# motherboard_Sheet.net
KiCad netlist of a schematic drawn in Altium Designer
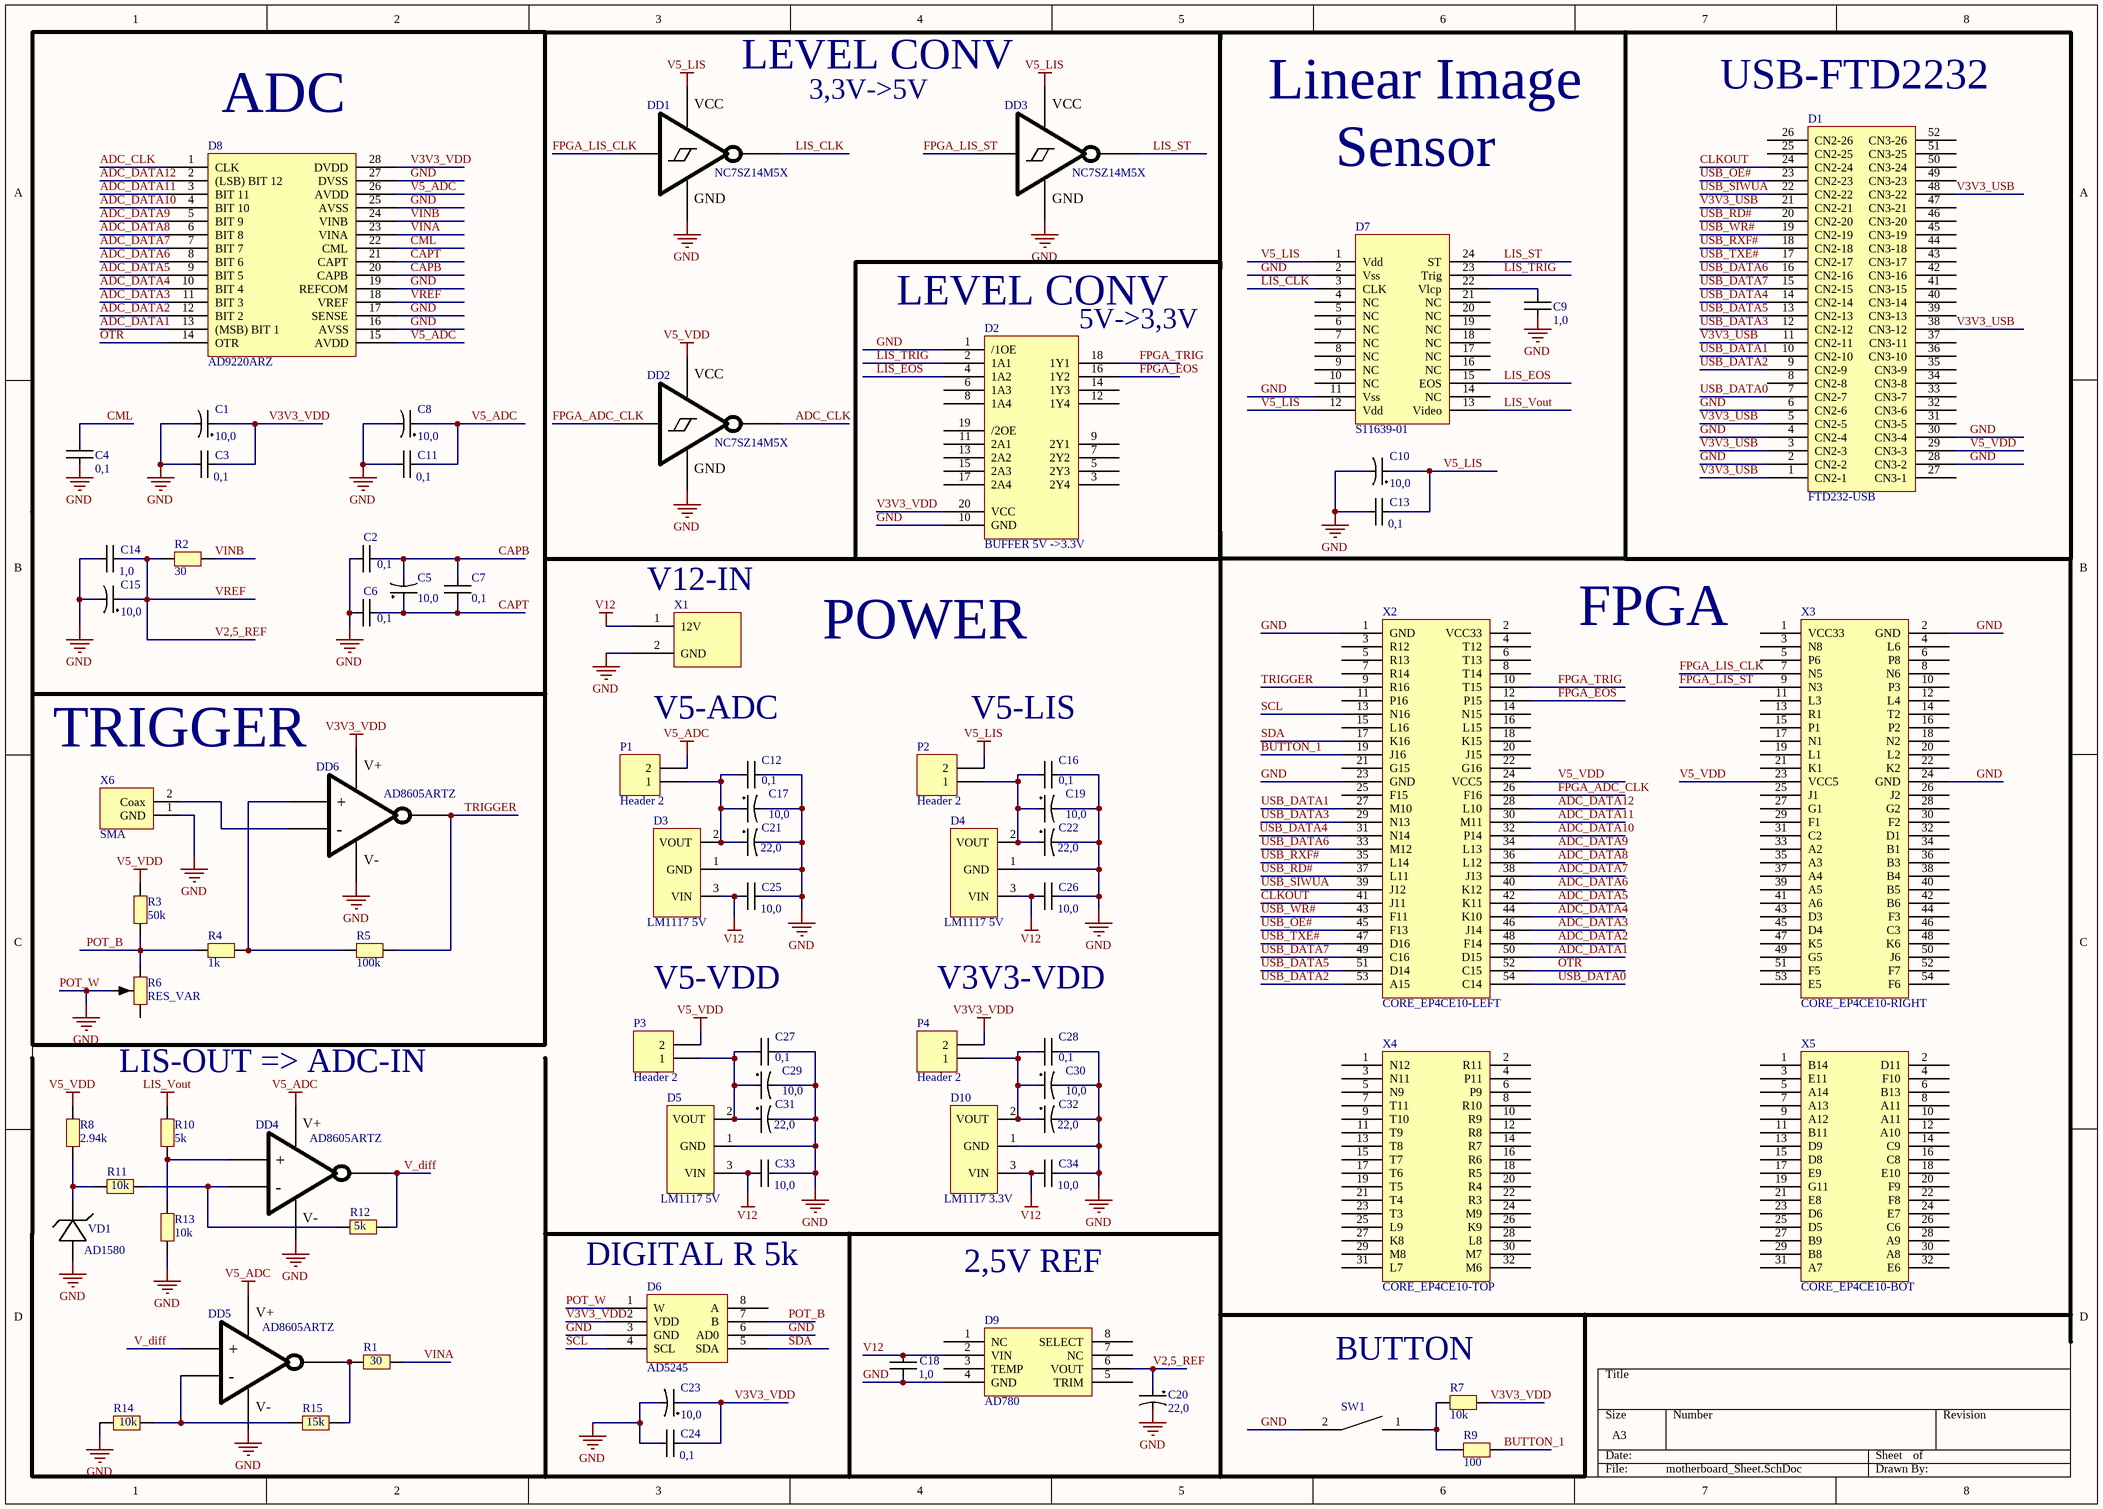
[diagram p0: motherboard_Sheet.SchDoc]

(export (version "E")
  (design (tool "Eeschema 10.0.6"))
  (components
    (comp (ref "C1")
      (value "10,0")
      (footprint "TYPE_C")
      (description "SMD")
      (libsource (lib "MIT_Schlib") (part "CAP_TANT"))
    )
    (comp (ref "C2")
      (value "0,1")
      (footprint "0805")
      (description "0805")
      (libsource (lib "MIT_Schlib") (part "CAP_SMALL"))
    )
    (comp (ref "C3")
      (value "0,1")
      (footprint "0805")
      (description "0805")
      (libsource (lib "MIT_Schlib") (part "CAP_SMALL"))
    )
    (comp (ref "C4")
      (value "0,1")
      (footprint "0805")
      (description "0805")
      (libsource (lib "MIT_Schlib") (part "CAP_SMALL"))
    )
    (comp (ref "C5")
      (value "10,0")
      (footprint "TYPE_C")
      (description "SMD")
      (libsource (lib "MIT_Schlib") (part "CAP_TANT"))
    )
    (comp (ref "C6")
      (value "0,1")
      (footprint "0805")
      (description "0805")
      (libsource (lib "MIT_Schlib") (part "CAP_SMALL"))
    )
    (comp (ref "C7")
      (value "0,1")
      (footprint "0805")
      (description "0805")
      (libsource (lib "MIT_Schlib") (part "CAP_SMALL"))
    )
    (comp (ref "C8")
      (value "10,0")
      (footprint "TYPE_C")
      (description "SMD")
      (libsource (lib "MIT_Schlib") (part "CAP_TANT"))
    )
    (comp (ref "C9")
      (value "1,0")
      (footprint "0805")
      (description "0805")
      (libsource (lib "MIT_Schlib") (part "CAP_SMALL"))
    )
    (comp (ref "C10")
      (value "10,0")
      (footprint "TYPE_C")
      (description "SMD")
      (libsource (lib "MIT_Schlib") (part "CAP_TANT"))
    )
    (comp (ref "C11")
      (value "0,1")
      (footprint "0805")
      (description "0805")
      (libsource (lib "MIT_Schlib") (part "CAP_SMALL"))
    )
    (comp (ref "C12")
      (value "0,1")
      (footprint "0805")
      (description "0805")
      (libsource (lib "MIT_Schlib") (part "CAP_SMALL"))
    )
    (comp (ref "C13")
      (value "0,1")
      (footprint "0805")
      (description "0805")
      (libsource (lib "MIT_Schlib") (part "CAP_SMALL"))
    )
    (comp (ref "C14")
      (value "1,0")
      (footprint "0805")
      (description "0805")
      (libsource (lib "MIT_Schlib") (part "CAP_SMALL"))
    )
    (comp (ref "C15")
      (value "10,0")
      (footprint "TYPE_C")
      (description "SMD")
      (libsource (lib "MIT_Schlib") (part "CAP_TANT"))
    )
    (comp (ref "C16")
      (value "0,1")
      (footprint "0805")
      (description "0805")
      (libsource (lib "MIT_Schlib") (part "CAP_SMALL"))
    )
    (comp (ref "C17")
      (value "10,0")
      (footprint "TYPE_C")
      (description "SMD")
      (libsource (lib "MIT_Schlib") (part "CAP_TANT"))
    )
    (comp (ref "C18")
      (value "1,0")
      (footprint "0805")
      (description "0805")
      (libsource (lib "MIT_Schlib") (part "CAP_SMALL"))
    )
    (comp (ref "C19")
      (value "10,0")
      (footprint "TYPE_C")
      (description "SMD")
      (libsource (lib "MIT_Schlib") (part "CAP_TANT"))
    )
    (comp (ref "C20")
      (value "22,0")
      (footprint "TYPE_C")
      (description "SMD")
      (libsource (lib "MIT_Schlib") (part "CAP_TANT"))
    )
    (comp (ref "C21")
      (value "22,0")
      (footprint "TYPE_C")
      (description "SMD")
      (libsource (lib "MIT_Schlib") (part "CAP_TANT"))
    )
    (comp (ref "C22")
      (value "22,0")
      (footprint "TYPE_C")
      (description "SMD")
      (libsource (lib "MIT_Schlib") (part "CAP_TANT"))
    )
    (comp (ref "C23")
      (value "10,0")
      (footprint "TYPE_C")
      (description "SMD")
      (libsource (lib "MIT_Schlib") (part "CAP_TANT"))
    )
    (comp (ref "C24")
      (value "0,1")
      (footprint "0805")
      (description "0805")
      (libsource (lib "MIT_Schlib") (part "CAP_SMALL"))
    )
    (comp (ref "C25")
      (value "10,0")
      (footprint "0805")
      (description "0805")
      (libsource (lib "MIT_Schlib") (part "CAP_SMALL"))
    )
    (comp (ref "C26")
      (value "10,0")
      (footprint "0805")
      (description "0805")
      (libsource (lib "MIT_Schlib") (part "CAP_SMALL"))
    )
    (comp (ref "C27")
      (value "0,1")
      (footprint "0805")
      (description "0805")
      (libsource (lib "MIT_Schlib") (part "CAP_SMALL"))
    )
    (comp (ref "C28")
      (value "0,1")
      (footprint "0805")
      (description "0805")
      (libsource (lib "MIT_Schlib") (part "CAP_SMALL"))
    )
    (comp (ref "C29")
      (value "10,0")
      (footprint "TYPE_C")
      (description "SMD")
      (libsource (lib "MIT_Schlib") (part "CAP_TANT"))
    )
    (comp (ref "C30")
      (value "10,0")
      (footprint "TYPE_C")
      (description "SMD")
      (libsource (lib "MIT_Schlib") (part "CAP_TANT"))
    )
    (comp (ref "C31")
      (value "22,0")
      (footprint "TYPE_C")
      (description "SMD")
      (libsource (lib "MIT_Schlib") (part "CAP_TANT"))
    )
    (comp (ref "C32")
      (value "22,0")
      (footprint "TYPE_C")
      (description "SMD")
      (libsource (lib "MIT_Schlib") (part "CAP_TANT"))
    )
    (comp (ref "C33")
      (value "10,0")
      (footprint "0805")
      (description "0805")
      (libsource (lib "MIT_Schlib") (part "CAP_SMALL"))
    )
    (comp (ref "C34")
      (value "10,0")
      (footprint "0805")
      (description "0805")
      (libsource (lib "MIT_Schlib") (part "CAP_SMALL"))
    )
    (comp (ref "D1")
      (value "FTD232-USB")
      (footprint "ftd232_minimodule")
      (libsource (lib "MIT_Schlib") (part "ftd232_minimodule"))
    )
    (comp (ref "D2")
      (value "BUFFER 5V ->3.3V")
      (footprint "SN74LVC244ADWR")
      (libsource (lib "MIT_Schlib") (part "SN74LVC244ADWR"))
    )
    (comp (ref "D3")
      (value "LM1117 5V")
      (footprint "TO-252")
      (description "LM1117-FIX")
      (libsource (lib "MIT_Schlib") (part "LM1117_FIX"))
    )
    (comp (ref "D4")
      (value "LM1117 5V")
      (footprint "TO-252")
      (description "LM1117-FIX")
      (libsource (lib "MIT_Schlib") (part "LM1117_FIX"))
    )
    (comp (ref "D5")
      (value "LM1117 5V")
      (footprint "TO-252")
      (description "LM1117-FIX")
      (libsource (lib "MIT_Schlib") (part "LM1117_FIX"))
    )
    (comp (ref "D6") (value "AD5245") (footprint "AD5245") (libsource (lib "MIT_Schlib") (part "AD5245")))
    (comp (ref "D7")
      (value "S11639-01")
      (footprint "s11639-01")
      (libsource (lib "MIT_Schlib") (part "S11639-01"))
    )
    (comp (ref "D8")
      (value "AD9220ARZ")
      (footprint "SOP28")
      (libsource (lib "MIT_Schlib") (part "AD9220ARZ"))
    )
    (comp (ref "D9") (value "AD780") (footprint "SOP8") (libsource (lib "MIT_Schlib") (part "AD780")))
    (comp (ref "D10")
      (value "LM1117 3.3V")
      (footprint "TO-252")
      (description "LM1117-FIX")
      (libsource (lib "MIT_Schlib") (part "LM1117_FIX"))
    )
    (comp (ref "DD1")
      (value "NC7SZ14M5X")
      (footprint "SOT-23-5")
      (libsource (lib "MIT_Schlib") (part "NC7SZ14M5X"))
    )
    (comp (ref "DD2")
      (value "NC7SZ14M5X")
      (footprint "SOT-23-5")
      (libsource (lib "MIT_Schlib") (part "NC7SZ14M5X"))
    )
    (comp (ref "DD3")
      (value "NC7SZ14M5X")
      (footprint "SOT-23-5")
      (libsource (lib "MIT_Schlib") (part "NC7SZ14M5X"))
    )
    (comp (ref "DD4")
      (value "AD8605ARTZ")
      (footprint "SOT-23-5")
      (libsource (lib "MIT_Schlib") (part "AD8605ARTZ"))
    )
    (comp (ref "DD5")
      (value "AD8605ARTZ")
      (footprint "SOT-23-5")
      (libsource (lib "MIT_Schlib") (part "AD8605ARTZ"))
    )
    (comp (ref "DD6")
      (value "AD8605ARTZ")
      (footprint "SOT-23-5")
      (libsource (lib "MIT_Schlib") (part "AD8605ARTZ"))
    )
    (comp (ref "P1")
      (value "Header 2")
      (footprint "HDR1X2")
      (description "Header, 2-Pin")
      (fields (field (name "PUBLISHER") "Altium Limited"))
      (libsource (lib "Miscellaneous Connectors") (part "Header 2"))
    )
    (comp (ref "P2")
      (value "Header 2")
      (footprint "HDR1X2")
      (description "Header, 2-Pin")
      (fields (field (name "PUBLISHER") "Altium Limited"))
      (libsource (lib "Miscellaneous Connectors") (part "Header 2"))
    )
    (comp (ref "P3")
      (value "Header 2")
      (footprint "HDR1X2")
      (description "Header, 2-Pin")
      (fields (field (name "PUBLISHER") "Altium Limited"))
      (libsource (lib "Miscellaneous Connectors") (part "Header 2"))
    )
    (comp (ref "P4")
      (value "Header 2")
      (footprint "HDR1X2")
      (description "Header, 2-Pin")
      (fields (field (name "PUBLISHER") "Altium Limited"))
      (libsource (lib "Miscellaneous Connectors") (part "Header 2"))
    )
    (comp (ref "R1")
      (value "30")
      (footprint "0805")
      (description "0805")
      (libsource (lib "MIT_Schlib") (part "RES0805"))
    )
    (comp (ref "R2")
      (value "30")
      (footprint "0805")
      (description "0805")
      (libsource (lib "MIT_Schlib") (part "RES0805"))
    )
    (comp (ref "R3")
      (value "50k")
      (footprint "0805")
      (description "0805")
      (libsource (lib "") (part "RES0805_1"))
    )
    (comp (ref "R4")
      (value "1k")
      (footprint "0805")
      (description "0805")
      (libsource (lib "") (part "RES0805_3"))
    )
    (comp (ref "R5")
      (value "100k")
      (footprint "0805")
      (description "0805")
      (libsource (lib "MIT_Schlib") (part "RES0805"))
    )
    (comp (ref "R6")
      (value "RES_VAR")
      (footprint "3006P")
      (description "PV36W102C (СП5-2ВБ) 1 кОм")
      (libsource (lib "MIT_Schlib") (part "RES_VAR"))
    )
    (comp (ref "R7")
      (value "10k")
      (footprint "0805")
      (description "0805")
      (libsource (lib "MIT_Schlib") (part "RES0805"))
    )
    (comp (ref "R8")
      (value "2.94k")
      (footprint "0805")
      (description "0805")
      (libsource (lib "") (part "RES0805_1"))
    )
    (comp (ref "R9")
      (value "100")
      (footprint "0805")
      (description "0805")
      (libsource (lib "MIT_Schlib") (part "RES0805"))
    )
    (comp (ref "R10")
      (value "5k")
      (footprint "0805")
      (description "0805")
      (libsource (lib "") (part "RES0805_1"))
    )
    (comp (ref "R11")
      (value "10k")
      (footprint "0805")
      (description "0805")
      (libsource (lib "MIT_Schlib") (part "RES0805"))
    )
    (comp (ref "R12")
      (value "5k")
      (footprint "0805")
      (description "0805")
      (libsource (lib "MIT_Schlib") (part "RES0805"))
    )
    (comp (ref "R13")
      (value "10k")
      (footprint "0805")
      (description "0805")
      (libsource (lib "") (part "RES0805_2"))
    )
    (comp (ref "R14")
      (value "10k")
      (footprint "0805")
      (description "0805")
      (libsource (lib "MIT_Schlib") (part "RES0805"))
    )
    (comp (ref "R15")
      (value "15k")
      (footprint "0805")
      (description "0805")
      (libsource (lib "MIT_Schlib") (part "RES0805"))
    )
    (comp (ref "SW1") (value "BUTTON") (footprint "BUTTON") (libsource (lib "MIT_Schlib") (part "BUTTON")))
    (comp (ref "VD1") (value "AD1580") (footprint "SOT-23") (libsource (lib "MIT_Schlib") (part "AD1580")))
    (comp (ref "X1")
      (value "12V POWER")
      (footprint "Robiton-DS-210")
      (libsource (lib "MIT_Schlib") (part "ROBITON_12V"))
    )
    (comp (ref "X2")
      (value "CORE_EP4CE10-LEFT")
      (footprint "CORE_EP4CE10-LEFT")
      (libsource (lib "MIT_Schlib") (part "CORE_EP4CE10-LEFT"))
    )
    (comp (ref "X3")
      (value "CORE_EP4CE10-RIGHT")
      (footprint "CORE_EP4CE10-RIGHT")
      (libsource (lib "MIT_Schlib") (part "CORE_EP4CE10-RIGHT"))
    )
    (comp (ref "X4")
      (value "CORE_EP4CE10-TOP")
      (footprint "CORE_EP4CE10-TOP")
      (libsource (lib "MIT_Schlib") (part "CORE_EP4CE10-TOP"))
    )
    (comp (ref "X5")
      (value "CORE_EP4CE10-BOT")
      (footprint "CORE_EP4CE10-BOT")
      (libsource (lib "MIT_Schlib") (part "CORE_EP4CE10-BOT"))
    )
    (comp (ref "X6") (value "SMA") (footprint "SMA") (libsource (lib "MIT_Schlib") (part "SMA")))
  )
  (nets
    (net (code "1") (name "/ADC_CLK") (class "Default")
      (node (ref "D8") (pin "1") (pinfunction "CLK_1") (pintype "passive"))
      (node (ref "DD2") (pin "4") (pinfunction "Y_OUT_4") (pintype "passive"))
    )
    (net (code "2") (name "/ADC_DATA1") (class "Default")
      (node (ref "D8") (pin "13") (pinfunction "(MSB)_BIT_1_13") (pintype "passive"))
      (node (ref "X2") (pin "50") (pinfunction "D15_50") (pintype "passive"))
    )
    (net (code "3") (name "/ADC_DATA2") (class "Default")
      (node (ref "D8") (pin "12") (pinfunction "BIT_2_12") (pintype "passive"))
      (node (ref "X2") (pin "48") (pinfunction "F14_48") (pintype "passive"))
    )
    (net (code "4") (name "/ADC_DATA3") (class "Default")
      (node (ref "D8") (pin "11") (pinfunction "BIT_3_11") (pintype "passive"))
      (node (ref "X2") (pin "46") (pinfunction "J14_46") (pintype "passive"))
    )
    (net (code "5") (name "/ADC_DATA4") (class "Default")
      (node (ref "D8") (pin "10") (pinfunction "BIT_4_10") (pintype "passive"))
      (node (ref "X2") (pin "44") (pinfunction "K10_44") (pintype "passive"))
    )
    (net (code "6") (name "/ADC_DATA5") (class "Default")
      (node (ref "D8") (pin "9") (pinfunction "BIT_5_9") (pintype "passive"))
      (node (ref "X2") (pin "42") (pinfunction "K11_42") (pintype "passive"))
    )
    (net (code "7") (name "/ADC_DATA6") (class "Default")
      (node (ref "D8") (pin "8") (pinfunction "BIT_6_8") (pintype "passive"))
      (node (ref "X2") (pin "40") (pinfunction "K12_40") (pintype "passive"))
    )
    (net (code "8") (name "/ADC_DATA7") (class "Default")
      (node (ref "D8") (pin "7") (pinfunction "BIT_7_7") (pintype "passive"))
      (node (ref "X2") (pin "38") (pinfunction "J13_38") (pintype "passive"))
    )
    (net (code "9") (name "/ADC_DATA8") (class "Default")
      (node (ref "D8") (pin "6") (pinfunction "BIT_8_6") (pintype "passive"))
      (node (ref "X2") (pin "36") (pinfunction "L12_36") (pintype "passive"))
    )
    (net (code "10") (name "/ADC_DATA9") (class "Default")
      (node (ref "D8") (pin "5") (pinfunction "BIT_9_5") (pintype "passive"))
      (node (ref "X2") (pin "34") (pinfunction "L13_34") (pintype "passive"))
    )
    (net (code "11") (name "/ADC_DATA10") (class "Default")
      (node (ref "D8") (pin "4") (pinfunction "BIT_10_4") (pintype "passive"))
      (node (ref "X2") (pin "32") (pinfunction "P14_32") (pintype "passive"))
    )
    (net (code "12") (name "/ADC_DATA11") (class "Default")
      (node (ref "D8") (pin "3") (pinfunction "BIT_11_3") (pintype "passive"))
      (node (ref "X2") (pin "30") (pinfunction "M11_30") (pintype "passive"))
    )
    (net (code "13") (name "/ADC_DATA12") (class "Default")
      (node (ref "D8") (pin "2") (pinfunction "(LSB)_BIT_12_2") (pintype "passive"))
      (node (ref "X2") (pin "28") (pinfunction "L10_28") (pintype "passive"))
    )
    (net (code "14") (name "/BUTTON_1") (class "Default")
      (node (ref "R9") (pin "2") (pinfunction "2_2") (pintype "passive"))
      (node (ref "X2") (pin "19") (pinfunction "J16_19") (pintype "passive"))
    )
    (net (code "15") (name "/CAPB") (class "Default")
      (node (ref "C2") (pin "1") (pinfunction "1_1") (pintype "passive"))
      (node (ref "C5") (pin "1") (pinfunction "1_1") (pintype "passive"))
      (node (ref "C7") (pin "2") (pinfunction "2_2") (pintype "passive"))
      (node (ref "D8") (pin "20") (pinfunction "CAPB_20") (pintype "passive"))
    )
    (net (code "16") (name "/CAPT") (class "Default")
      (node (ref "C5") (pin "2") (pinfunction "2_2") (pintype "passive"))
      (node (ref "C6") (pin "1") (pinfunction "1_1") (pintype "passive"))
      (node (ref "C7") (pin "1") (pinfunction "1_1") (pintype "passive"))
      (node (ref "D8") (pin "21") (pinfunction "CAPT_21") (pintype "passive"))
    )
    (net (code "17") (name "/CLKOUT") (class "Default")
      (node (ref "D1") (pin "24") (pinfunction "CN2-24_24") (pintype "passive"))
      (node (ref "X2") (pin "41") (pinfunction "J11_41") (pintype "passive"))
    )
    (net (code "18") (name "/CML") (class "Default")
      (node (ref "C4") (pin "2") (pinfunction "2_2") (pintype "passive"))
      (node (ref "D8") (pin "22") (pinfunction "CML_22") (pintype "passive"))
    )
    (net (code "19") (name "/FPGA_ADC_CLK") (class "Default")
      (node (ref "DD2") (pin "2") (pinfunction "A_IN_2") (pintype "passive"))
      (node (ref "X2") (pin "26") (pinfunction "F16_26") (pintype "passive"))
    )
    (net (code "20") (name "/FPGA_EOS") (class "Default")
      (node (ref "D2") (pin "16") (pinfunction "1Y2_16") (pintype "passive"))
      (node (ref "X2") (pin "12") (pinfunction "P15_12") (pintype "passive"))
    )
    (net (code "21") (name "/FPGA_LIS_CLK") (class "Default")
      (node (ref "DD1") (pin "2") (pinfunction "A_IN_2") (pintype "passive"))
      (node (ref "X3") (pin "7") (pinfunction "N5_7") (pintype "passive"))
    )
    (net (code "22") (name "/FPGA_LIS_ST") (class "Default")
      (node (ref "DD3") (pin "2") (pinfunction "A_IN_2") (pintype "passive"))
      (node (ref "X3") (pin "9") (pinfunction "N3_9") (pintype "passive"))
    )
    (net (code "23") (name "/FPGA_TRIG") (class "Default")
      (node (ref "D2") (pin "18") (pinfunction "1Y1_18") (pintype "passive"))
      (node (ref "X2") (pin "10") (pinfunction "T15_10") (pintype "passive"))
    )
    (net (code "24") (name "/LIS_CLK") (class "Default")
      (node (ref "D7") (pin "3") (pinfunction "CLK_3") (pintype "passive"))
      (node (ref "DD1") (pin "4") (pinfunction "Y_OUT_4") (pintype "passive"))
    )
    (net (code "25") (name "/LIS_EOS") (class "Default")
      (node (ref "D2") (pin "4") (pinfunction "1A2_4") (pintype "passive"))
      (node (ref "D7") (pin "15") (pinfunction "EOS_15") (pintype "passive"))
    )
    (net (code "26") (name "/LIS_ST") (class "Default")
      (node (ref "D7") (pin "24") (pinfunction "ST_24") (pintype "passive"))
      (node (ref "DD3") (pin "4") (pinfunction "Y_OUT_4") (pintype "passive"))
    )
    (net (code "27") (name "/LIS_TRIG") (class "Default")
      (node (ref "D2") (pin "2") (pinfunction "1A1_2") (pintype "passive"))
      (node (ref "D7") (pin "23") (pinfunction "Trig_23") (pintype "passive"))
    )
    (net (code "28") (name "/OTR") (class "Default")
      (node (ref "D8") (pin "14") (pinfunction "OTR_14") (pintype "passive"))
      (node (ref "X2") (pin "52") (pinfunction "C15_52") (pintype "passive"))
    )
    (net (code "29") (name "/POT_B") (class "Default")
      (node (ref "D6") (pin "7") (pinfunction "B_7") (pintype "passive"))
      (node (ref "R3") (pin "1") (pinfunction "1_1") (pintype "passive"))
      (node (ref "R4") (pin "2") (pinfunction "2_2") (pintype "passive"))
      (node (ref "R6") (pin "1") (pinfunction "1_1") (pintype "passive"))
    )
    (net (code "30") (name "/SCL") (class "Default")
      (node (ref "D6") (pin "4") (pinfunction "SCL_4") (pintype "passive"))
      (node (ref "X2") (pin "13") (pinfunction "N16_13") (pintype "passive"))
    )
    (net (code "31") (name "/SDA") (class "Default")
      (node (ref "D6") (pin "5") (pinfunction "SDA_5") (pintype "passive"))
      (node (ref "X2") (pin "17") (pinfunction "K16_17") (pintype "passive"))
    )
    (net (code "32") (name "/TRIGGER") (class "Default")
      (node (ref "DD6") (pin "1") (pinfunction "OUT_1") (pintype "passive"))
      (node (ref "R5") (pin "2") (pinfunction "2_2") (pintype "passive"))
      (node (ref "X2") (pin "9") (pinfunction "R16_9") (pintype "passive"))
    )
    (net (code "33") (name "/USB_DATA0") (class "Default")
      (node (ref "D1") (pin "7") (pinfunction "CN2-7_7") (pintype "passive"))
      (node (ref "X2") (pin "54") (pinfunction "C14_54") (pintype "passive"))
    )
    (net (code "34") (name "/USB_DATA1") (class "Default")
      (node (ref "D1") (pin "10") (pinfunction "CN2-10_10") (pintype "passive"))
      (node (ref "X2") (pin "27") (pinfunction "M10_27") (pintype "passive"))
    )
    (net (code "35") (name "/USB_DATA2") (class "Default")
      (node (ref "D1") (pin "9") (pinfunction "CN2-9_9") (pintype "passive"))
      (node (ref "X2") (pin "53") (pinfunction "A15_53") (pintype "passive"))
    )
    (net (code "36") (name "/USB_DATA3") (class "Default")
      (node (ref "D1") (pin "12") (pinfunction "CN2-12_12") (pintype "passive"))
      (node (ref "X2") (pin "29") (pinfunction "N13_29") (pintype "passive"))
    )
    (net (code "37") (name "/USB_DATA4") (class "Default")
      (node (ref "D1") (pin "14") (pinfunction "CN2-14_14") (pintype "passive"))
      (node (ref "X2") (pin "31") (pinfunction "N14_31") (pintype "passive"))
    )
    (net (code "38") (name "/USB_DATA5") (class "Default")
      (node (ref "D1") (pin "13") (pinfunction "CN2-13_13") (pintype "passive"))
      (node (ref "X2") (pin "51") (pinfunction "D14_51") (pintype "passive"))
    )
    (net (code "39") (name "/USB_DATA6") (class "Default")
      (node (ref "D1") (pin "16") (pinfunction "CN2-16_16") (pintype "passive"))
      (node (ref "X2") (pin "33") (pinfunction "M12_33") (pintype "passive"))
    )
    (net (code "40") (name "/USB_DATA7") (class "Default")
      (node (ref "D1") (pin "15") (pinfunction "CN2-15_15") (pintype "passive"))
      (node (ref "X2") (pin "49") (pinfunction "C16_49") (pintype "passive"))
    )
    (net (code "41") (name "/USB_OE#") (class "Default")
      (node (ref "D1") (pin "23") (pinfunction "CN2-23_23") (pintype "passive"))
      (node (ref "X2") (pin "45") (pinfunction "F13_45") (pintype "passive"))
    )
    (net (code "42") (name "/USB_RD#") (class "Default")
      (node (ref "D1") (pin "20") (pinfunction "CN2-20_20") (pintype "passive"))
      (node (ref "X2") (pin "37") (pinfunction "L11_37") (pintype "passive"))
    )
    (net (code "43") (name "/USB_RXF#") (class "Default")
      (node (ref "D1") (pin "18") (pinfunction "CN2-18_18") (pintype "passive"))
      (node (ref "X2") (pin "35") (pinfunction "L14_35") (pintype "passive"))
    )
    (net (code "44") (name "/USB_SIWUA") (class "Default")
      (node (ref "D1") (pin "22") (pinfunction "CN2-22_22") (pintype "passive"))
      (node (ref "X2") (pin "39") (pinfunction "J12_39") (pintype "passive"))
    )
    (net (code "45") (name "/USB_TXE#") (class "Default")
      (node (ref "D1") (pin "17") (pinfunction "CN2-17_17") (pintype "passive"))
      (node (ref "X2") (pin "47") (pinfunction "D16_47") (pintype "passive"))
    )
    (net (code "46") (name "/USB_WR#") (class "Default")
      (node (ref "D1") (pin "19") (pinfunction "CN2-19_19") (pintype "passive"))
      (node (ref "X2") (pin "43") (pinfunction "F11_43") (pintype "passive"))
    )
    (net (code "47") (name "/V2,5_REF") (class "Default")
      (node (ref "C14") (pin "2") (pinfunction "2_2") (pintype "passive"))
      (node (ref "C15") (pin "2") (pinfunction "2_2") (pintype "passive"))
      (node (ref "C20") (pin "2") (pinfunction "2_2") (pintype "passive"))
      (node (ref "D8") (pin "18") (pinfunction "VREF_18") (pintype "passive"))
      (node (ref "D9") (pin "6") (pinfunction "VOUT_6") (pintype "passive"))
      (node (ref "R2") (pin "1") (pinfunction "1_1") (pintype "passive"))
    )
    (net (code "48") (name "/V3V3_USB") (class "Default")
      (node (ref "D1") (pin "1") (pinfunction "CN2-1_1") (pintype "passive"))
      (node (ref "D1") (pin "11") (pinfunction "CN2-11_11") (pintype "passive"))
      (node (ref "D1") (pin "21") (pinfunction "CN2-21_21") (pintype "passive"))
      (node (ref "D1") (pin "3") (pinfunction "CN2-3_3") (pintype "passive"))
      (node (ref "D1") (pin "38") (pinfunction "CN3-12_38") (pintype "passive"))
      (node (ref "D1") (pin "48") (pinfunction "CN3-22_48") (pintype "passive"))
      (node (ref "D1") (pin "5") (pinfunction "CN2-5_5") (pintype "passive"))
    )
    (net (code "49") (name "/VINA") (class "Default")
      (node (ref "D8") (pin "23") (pinfunction "VINA_23") (pintype "passive"))
      (node (ref "R1") (pin "2") (pinfunction "2_2") (pintype "passive"))
    )
    (net (code "50") (name "/VINB") (class "Default")
      (node (ref "D8") (pin "24") (pinfunction "VINB_24") (pintype "passive"))
      (node (ref "R2") (pin "2") (pinfunction "2_2") (pintype "passive"))
    )
    (net (code "51") (name "/V_diff") (class "Default")
      (node (ref "DD4") (pin "1") (pinfunction "OUT_1") (pintype "passive"))
      (node (ref "DD5") (pin "3") (pinfunction "+_3") (pintype "passive"))
      (node (ref "R12") (pin "2") (pinfunction "2_2") (pintype "passive"))
    )
    (net (code "52") (name "GND") (class "Default")
      (node (ref "C1") (pin "1") (pinfunction "1_1") (pintype "passive"))
      (node (ref "C10") (pin "1") (pinfunction "1_1") (pintype "passive"))
      (node (ref "C11") (pin "1") (pinfunction "1_1") (pintype "passive"))
      (node (ref "C12") (pin "1") (pinfunction "1_1") (pintype "passive"))
      (node (ref "C13") (pin "1") (pinfunction "1_1") (pintype "passive"))
      (node (ref "C14") (pin "1") (pinfunction "1_1") (pintype "passive"))
      (node (ref "C15") (pin "1") (pinfunction "1_1") (pintype "passive"))
      (node (ref "C16") (pin "1") (pinfunction "1_1") (pintype "passive"))
      (node (ref "C17") (pin "1") (pinfunction "1_1") (pintype "passive"))
      (node (ref "C18") (pin "1") (pinfunction "1_1") (pintype "passive"))
      (node (ref "C19") (pin "1") (pinfunction "1_1") (pintype "passive"))
      (node (ref "C2") (pin "2") (pinfunction "2_2") (pintype "passive"))
      (node (ref "C20") (pin "1") (pinfunction "1_1") (pintype "passive"))
      (node (ref "C21") (pin "1") (pinfunction "1_1") (pintype "passive"))
      (node (ref "C22") (pin "1") (pinfunction "1_1") (pintype "passive"))
      (node (ref "C23") (pin "1") (pinfunction "1_1") (pintype "passive"))
      (node (ref "C24") (pin "1") (pinfunction "1_1") (pintype "passive"))
      (node (ref "C25") (pin "2") (pinfunction "2_2") (pintype "passive"))
      (node (ref "C26") (pin "2") (pinfunction "2_2") (pintype "passive"))
      (node (ref "C27") (pin "1") (pinfunction "1_1") (pintype "passive"))
      (node (ref "C28") (pin "1") (pinfunction "1_1") (pintype "passive"))
      (node (ref "C29") (pin "1") (pinfunction "1_1") (pintype "passive"))
      (node (ref "C3") (pin "1") (pinfunction "1_1") (pintype "passive"))
      (node (ref "C30") (pin "1") (pinfunction "1_1") (pintype "passive"))
      (node (ref "C31") (pin "1") (pinfunction "1_1") (pintype "passive"))
      (node (ref "C32") (pin "1") (pinfunction "1_1") (pintype "passive"))
      (node (ref "C33") (pin "2") (pinfunction "2_2") (pintype "passive"))
      (node (ref "C34") (pin "2") (pinfunction "2_2") (pintype "passive"))
      (node (ref "C4") (pin "1") (pinfunction "1_1") (pintype "passive"))
      (node (ref "C6") (pin "2") (pinfunction "2_2") (pintype "passive"))
      (node (ref "C8") (pin "1") (pinfunction "1_1") (pintype "passive"))
      (node (ref "C9") (pin "2") (pinfunction "2_2") (pintype "passive"))
      (node (ref "D1") (pin "2") (pinfunction "CN2-2_2") (pintype "passive"))
      (node (ref "D1") (pin "28") (pinfunction "CN3-2_28") (pintype "passive"))
      (node (ref "D1") (pin "30") (pinfunction "CN3-4_30") (pintype "passive"))
      (node (ref "D1") (pin "4") (pinfunction "CN2-4_4") (pintype "passive"))
      (node (ref "D1") (pin "6") (pinfunction "CN2-6_6") (pintype "passive"))
      (node (ref "D10") (pin "1") (pinfunction "GND_1") (pintype "passive"))
      (node (ref "D2") (pin "1") (pinfunction "/1OE_1") (pintype "passive"))
      (node (ref "D2") (pin "10") (pinfunction "GND_10") (pintype "passive"))
      (node (ref "D3") (pin "1") (pinfunction "GND_1") (pintype "passive"))
      (node (ref "D4") (pin "1") (pinfunction "GND_1") (pintype "passive"))
      (node (ref "D5") (pin "1") (pinfunction "GND_1") (pintype "passive"))
      (node (ref "D6") (pin "1") (pinfunction "W_1") (pintype "passive"))
      (node (ref "D6") (pin "3") (pinfunction "GND_3") (pintype "passive"))
      (node (ref "D6") (pin "6") (pinfunction "AD0_6") (pintype "passive"))
      (node (ref "D7") (pin "11") (pinfunction "Vss_11") (pintype "passive"))
      (node (ref "D7") (pin "2") (pinfunction "Vss_2") (pintype "passive"))
      (node (ref "D8") (pin "16") (pinfunction "AVSS_16") (pintype "passive"))
      (node (ref "D8") (pin "17") (pinfunction "SENSE_17") (pintype "passive"))
      (node (ref "D8") (pin "19") (pinfunction "REFCOM_19") (pintype "passive"))
      (node (ref "D8") (pin "25") (pinfunction "AVSS_25") (pintype "passive"))
      (node (ref "D8") (pin "27") (pinfunction "DVSS_27") (pintype "passive"))
      (node (ref "D9") (pin "4") (pinfunction "GND_4") (pintype "passive"))
      (node (ref "DD1") (pin "3") (pinfunction "GND_3") (pintype "passive"))
      (node (ref "DD2") (pin "3") (pinfunction "GND_3") (pintype "passive"))
      (node (ref "DD3") (pin "3") (pinfunction "GND_3") (pintype "passive"))
      (node (ref "DD4") (pin "2") (pinfunction "V-_2") (pintype "passive"))
      (node (ref "DD5") (pin "2") (pinfunction "V-_2") (pintype "passive"))
      (node (ref "DD6") (pin "2") (pinfunction "V-_2") (pintype "passive"))
      (node (ref "R13") (pin "2") (pinfunction "2_2") (pintype "passive"))
      (node (ref "R14") (pin "1") (pinfunction "1_1") (pintype "passive"))
      (node (ref "R6") (pin "2") (pinfunction "2_2") (pintype "passive"))
      (node (ref "SW1") (pin "2") (pinfunction "2_2") (pintype "passive"))
      (node (ref "VD1") (pin "2") (pinfunction "V-_2") (pintype "passive"))
      (node (ref "X1") (pin "2") (pinfunction "GND_2") (pintype "passive"))
      (node (ref "X2") (pin "1") (pinfunction "GND_1") (pintype "passive"))
      (node (ref "X2") (pin "23") (pinfunction "GND_23") (pintype "passive"))
      (node (ref "X3") (pin "2") (pinfunction "GND_2") (pintype "passive"))
      (node (ref "X3") (pin "24") (pinfunction "GND_24") (pintype "passive"))
      (node (ref "X6") (pin "1") (pinfunction "GND_1") (pintype "passive"))
    )
    (net (code "53") (name "LIS_Vout") (class "Default")
      (node (ref "D7") (pin "13") (pinfunction "Video_13") (pintype "passive"))
      (node (ref "R10") (pin "2") (pinfunction "2_2") (pintype "passive"))
    )
    (net (code "54") (name "Net-(D3-VOUT)") (class "Default")
      (node (ref "C12") (pin "2") (pinfunction "2_2") (pintype "passive"))
      (node (ref "C17") (pin "2") (pinfunction "2_2") (pintype "passive"))
      (node (ref "C21") (pin "2") (pinfunction "2_2") (pintype "passive"))
      (node (ref "D3") (pin "2") (pinfunction "VOUT_2") (pintype "passive"))
      (node (ref "P1") (pin "1") (pinfunction "1_1") (pintype "passive"))
    )
    (net (code "55") (name "Net-(D4-VOUT)") (class "Default")
      (node (ref "C16") (pin "2") (pinfunction "2_2") (pintype "passive"))
      (node (ref "C19") (pin "2") (pinfunction "2_2") (pintype "passive"))
      (node (ref "C22") (pin "2") (pinfunction "2_2") (pintype "passive"))
      (node (ref "D4") (pin "2") (pinfunction "VOUT_2") (pintype "passive"))
      (node (ref "P2") (pin "1") (pinfunction "1_1") (pintype "passive"))
    )
    (net (code "56") (name "Net-(D5-VOUT)") (class "Default")
      (node (ref "C27") (pin "2") (pinfunction "2_2") (pintype "passive"))
      (node (ref "C29") (pin "2") (pinfunction "2_2") (pintype "passive"))
      (node (ref "C31") (pin "2") (pinfunction "2_2") (pintype "passive"))
      (node (ref "D5") (pin "2") (pinfunction "VOUT_2") (pintype "passive"))
      (node (ref "P3") (pin "1") (pinfunction "1_1") (pintype "passive"))
    )
    (net (code "57") (name "Net-(D7-Vlcp)") (class "Default")
      (node (ref "C9") (pin "1") (pinfunction "1_1") (pintype "passive"))
      (node (ref "D7") (pin "22") (pinfunction "Vlcp_22") (pintype "passive"))
    )
    (net (code "58") (name "Net-(D10-VOUT)") (class "Default")
      (node (ref "C28") (pin "2") (pinfunction "2_2") (pintype "passive"))
      (node (ref "C30") (pin "2") (pinfunction "2_2") (pintype "passive"))
      (node (ref "C32") (pin "2") (pinfunction "2_2") (pintype "passive"))
      (node (ref "D10") (pin "2") (pinfunction "VOUT_2") (pintype "passive"))
      (node (ref "P4") (pin "1") (pinfunction "1_1") (pintype "passive"))
    )
    (net (code "59") (name "Net-(DD4-+)") (class "Default")
      (node (ref "DD4") (pin "3") (pinfunction "+_3") (pintype "passive"))
      (node (ref "R10") (pin "1") (pinfunction "1_1") (pintype "passive"))
      (node (ref "R13") (pin "1") (pinfunction "1_1") (pintype "passive"))
    )
    (net (code "60") (name "Net-(DD4--)") (class "Default")
      (node (ref "DD4") (pin "4") (pinfunction "-_4") (pintype "passive"))
      (node (ref "R11") (pin "2") (pinfunction "2_2") (pintype "passive"))
      (node (ref "R12") (pin "1") (pinfunction "1_1") (pintype "passive"))
    )
    (net (code "61") (name "Net-(DD5--)") (class "Default")
      (node (ref "DD5") (pin "4") (pinfunction "-_4") (pintype "passive"))
      (node (ref "R14") (pin "2") (pinfunction "2_2") (pintype "passive"))
      (node (ref "R15") (pin "1") (pinfunction "1_1") (pintype "passive"))
    )
    (net (code "62") (name "Net-(DD5-OUT)") (class "Default")
      (node (ref "DD5") (pin "1") (pinfunction "OUT_1") (pintype "passive"))
      (node (ref "R1") (pin "1") (pinfunction "1_1") (pintype "passive"))
      (node (ref "R15") (pin "2") (pinfunction "2_2") (pintype "passive"))
    )
    (net (code "63") (name "Net-(DD6-+)") (class "Default")
      (node (ref "DD6") (pin "3") (pinfunction "+_3") (pintype "passive"))
      (node (ref "R4") (pin "1") (pinfunction "1_1") (pintype "passive"))
      (node (ref "R5") (pin "1") (pinfunction "1_1") (pintype "passive"))
    )
    (net (code "64") (name "Net-(DD6--)") (class "Default")
      (node (ref "DD6") (pin "4") (pinfunction "-_4") (pintype "passive"))
      (node (ref "X6") (pin "2") (pinfunction "Coax_2") (pintype "passive"))
    )
    (net (code "65") (name "Net-(R7-Pad1)") (class "Default")
      (node (ref "R7") (pin "1") (pinfunction "1_1") (pintype "passive"))
      (node (ref "R9") (pin "1") (pinfunction "1_1") (pintype "passive"))
      (node (ref "SW1") (pin "1") (pinfunction "1_1") (pintype "passive"))
    )
    (net (code "66") (name "Net-(VD1-V+)") (class "Default")
      (node (ref "R11") (pin "1") (pinfunction "1_1") (pintype "passive"))
      (node (ref "R8") (pin "1") (pinfunction "1_1") (pintype "passive"))
      (node (ref "VD1") (pin "1") (pinfunction "V+_1") (pintype "passive"))
    )
    (net (code "67") (name "V3V3_VDD") (class "Default")
      (node (ref "C1") (pin "2") (pinfunction "2_2") (pintype "passive"))
      (node (ref "C23") (pin "2") (pinfunction "2_2") (pintype "passive"))
      (node (ref "C24") (pin "2") (pinfunction "2_2") (pintype "passive"))
      (node (ref "C3") (pin "2") (pinfunction "2_2") (pintype "passive"))
      (node (ref "D2") (pin "20") (pinfunction "VCC_20") (pintype "passive"))
      (node (ref "D6") (pin "2") (pinfunction "VDD_2") (pintype "passive"))
      (node (ref "D8") (pin "28") (pinfunction "DVDD_28") (pintype "passive"))
      (node (ref "DD6") (pin "5") (pinfunction "V+_5") (pintype "passive"))
      (node (ref "P4") (pin "2") (pinfunction "2_2") (pintype "passive"))
      (node (ref "R7") (pin "2") (pinfunction "2_2") (pintype "passive"))
    )
    (net (code "68") (name "V5_ADC") (class "Default")
      (node (ref "C11") (pin "2") (pinfunction "2_2") (pintype "passive"))
      (node (ref "C8") (pin "2") (pinfunction "2_2") (pintype "passive"))
      (node (ref "D8") (pin "15") (pinfunction "AVDD_15") (pintype "passive"))
      (node (ref "D8") (pin "26") (pinfunction "AVDD_26") (pintype "passive"))
      (node (ref "DD4") (pin "5") (pinfunction "V+_5") (pintype "passive"))
      (node (ref "DD5") (pin "5") (pinfunction "V+_5") (pintype "passive"))
      (node (ref "P1") (pin "2") (pinfunction "2_2") (pintype "passive"))
    )
    (net (code "69") (name "V5_LIS") (class "Default")
      (node (ref "C10") (pin "2") (pinfunction "2_2") (pintype "passive"))
      (node (ref "C13") (pin "2") (pinfunction "2_2") (pintype "passive"))
      (node (ref "D7") (pin "1") (pinfunction "Vdd_1") (pintype "passive"))
      (node (ref "D7") (pin "12") (pinfunction "Vdd_12") (pintype "passive"))
      (node (ref "DD1") (pin "5") (pinfunction "VCC_5") (pintype "passive"))
      (node (ref "DD3") (pin "5") (pinfunction "VCC_5") (pintype "passive"))
      (node (ref "P2") (pin "2") (pinfunction "2_2") (pintype "passive"))
    )
    (net (code "70") (name "V5_VDD") (class "Default")
      (node (ref "D1") (pin "29") (pinfunction "CN3-3_29") (pintype "passive"))
      (node (ref "DD2") (pin "5") (pinfunction "VCC_5") (pintype "passive"))
      (node (ref "P3") (pin "2") (pinfunction "2_2") (pintype "passive"))
      (node (ref "R3") (pin "2") (pinfunction "2_2") (pintype "passive"))
      (node (ref "R8") (pin "2") (pinfunction "2_2") (pintype "passive"))
      (node (ref "X2") (pin "24") (pinfunction "VCC5_24") (pintype "passive"))
      (node (ref "X3") (pin "23") (pinfunction "VCC5_23") (pintype "passive"))
    )
    (net (code "71") (name "V12") (class "Default")
      (node (ref "C18") (pin "2") (pinfunction "2_2") (pintype "passive"))
      (node (ref "C25") (pin "1") (pinfunction "1_1") (pintype "passive"))
      (node (ref "C26") (pin "1") (pinfunction "1_1") (pintype "passive"))
      (node (ref "C33") (pin "1") (pinfunction "1_1") (pintype "passive"))
      (node (ref "C34") (pin "1") (pinfunction "1_1") (pintype "passive"))
      (node (ref "D10") (pin "3") (pinfunction "VIN_3") (pintype "passive"))
      (node (ref "D3") (pin "3") (pinfunction "VIN_3") (pintype "passive"))
      (node (ref "D4") (pin "3") (pinfunction "VIN_3") (pintype "passive"))
      (node (ref "D5") (pin "3") (pinfunction "VIN_3") (pintype "passive"))
      (node (ref "D9") (pin "2") (pinfunction "VIN_2") (pintype "passive"))
      (node (ref "X1") (pin "1") (pinfunction "12V_1") (pintype "passive"))
    )
    (net (code "72") (name "unconnected-(D1-CN2-8-Pad8)") (class "Default")
      (node (ref "D1") (pin "8") (pinfunction "CN2-8_8") (pintype "passive"))
    )
    (net (code "73") (name "unconnected-(D1-CN2-25-Pad25)") (class "Default")
      (node (ref "D1") (pin "25") (pinfunction "CN2-25_25") (pintype "passive"))
    )
    (net (code "74") (name "unconnected-(D1-CN2-26-Pad26)") (class "Default")
      (node (ref "D1") (pin "26") (pinfunction "CN2-26_26") (pintype "passive"))
    )
    (net (code "75") (name "unconnected-(D1-CN3-1-Pad27)") (class "Default")
      (node (ref "D1") (pin "27") (pinfunction "CN3-1_27") (pintype "passive"))
    )
    (net (code "76") (name "unconnected-(D1-CN3-5-Pad31)") (class "Default")
      (node (ref "D1") (pin "31") (pinfunction "CN3-5_31") (pintype "passive"))
    )
    (net (code "77") (name "unconnected-(D1-CN3-6-Pad32)") (class "Default")
      (node (ref "D1") (pin "32") (pinfunction "CN3-6_32") (pintype "passive"))
    )
    (net (code "78") (name "unconnected-(D1-CN3-7-Pad33)") (class "Default")
      (node (ref "D1") (pin "33") (pinfunction "CN3-7_33") (pintype "passive"))
    )
    (net (code "79") (name "unconnected-(D1-CN3-8-Pad34)") (class "Default")
      (node (ref "D1") (pin "34") (pinfunction "CN3-8_34") (pintype "passive"))
    )
    (net (code "80") (name "unconnected-(D1-CN3-9-Pad35)") (class "Default")
      (node (ref "D1") (pin "35") (pinfunction "CN3-9_35") (pintype "passive"))
    )
    (net (code "81") (name "unconnected-(D1-CN3-10-Pad36)") (class "Default")
      (node (ref "D1") (pin "36") (pinfunction "CN3-10_36") (pintype "passive"))
    )
    (net (code "82") (name "unconnected-(D1-CN3-11-Pad37)") (class "Default")
      (node (ref "D1") (pin "37") (pinfunction "CN3-11_37") (pintype "passive"))
    )
    (net (code "83") (name "unconnected-(D1-CN3-13-Pad39)") (class "Default")
      (node (ref "D1") (pin "39") (pinfunction "CN3-13_39") (pintype "passive"))
    )
    (net (code "84") (name "unconnected-(D1-CN3-14-Pad40)") (class "Default")
      (node (ref "D1") (pin "40") (pinfunction "CN3-14_40") (pintype "passive"))
    )
    (net (code "85") (name "unconnected-(D1-CN3-15-Pad41)") (class "Default")
      (node (ref "D1") (pin "41") (pinfunction "CN3-15_41") (pintype "passive"))
    )
    (net (code "86") (name "unconnected-(D1-CN3-16-Pad42)") (class "Default")
      (node (ref "D1") (pin "42") (pinfunction "CN3-16_42") (pintype "passive"))
    )
    (net (code "87") (name "unconnected-(D1-CN3-17-Pad43)") (class "Default")
      (node (ref "D1") (pin "43") (pinfunction "CN3-17_43") (pintype "passive"))
    )
    (net (code "88") (name "unconnected-(D1-CN3-18-Pad44)") (class "Default")
      (node (ref "D1") (pin "44") (pinfunction "CN3-18_44") (pintype "passive"))
    )
    (net (code "89") (name "unconnected-(D1-CN3-19-Pad45)") (class "Default")
      (node (ref "D1") (pin "45") (pinfunction "CN3-19_45") (pintype "passive"))
    )
    (net (code "90") (name "unconnected-(D1-CN3-20-Pad46)") (class "Default")
      (node (ref "D1") (pin "46") (pinfunction "CN3-20_46") (pintype "passive"))
    )
    (net (code "91") (name "unconnected-(D1-CN3-21-Pad47)") (class "Default")
      (node (ref "D1") (pin "47") (pinfunction "CN3-21_47") (pintype "passive"))
    )
    (net (code "92") (name "unconnected-(D1-CN3-23-Pad49)") (class "Default")
      (node (ref "D1") (pin "49") (pinfunction "CN3-23_49") (pintype "passive"))
    )
    (net (code "93") (name "unconnected-(D1-CN3-24-Pad50)") (class "Default")
      (node (ref "D1") (pin "50") (pinfunction "CN3-24_50") (pintype "passive"))
    )
    (net (code "94") (name "unconnected-(D1-CN3-25-Pad51)") (class "Default")
      (node (ref "D1") (pin "51") (pinfunction "CN3-25_51") (pintype "passive"))
    )
    (net (code "95") (name "unconnected-(D1-CN3-26-Pad52)") (class "Default")
      (node (ref "D1") (pin "52") (pinfunction "CN3-26_52") (pintype "passive"))
    )
    (net (code "96") (name "unconnected-(D2-1A3-Pad6)") (class "Default")
      (node (ref "D2") (pin "6") (pinfunction "1A3_6") (pintype "passive"))
    )
    (net (code "97") (name "unconnected-(D2-1A4-Pad8)") (class "Default")
      (node (ref "D2") (pin "8") (pinfunction "1A4_8") (pintype "passive"))
    )
    (net (code "98") (name "unconnected-(D2-1Y3-Pad14)") (class "Default")
      (node (ref "D2") (pin "14") (pinfunction "1Y3_14") (pintype "passive"))
    )
    (net (code "99") (name "unconnected-(D2-1Y4-Pad12)") (class "Default")
      (node (ref "D2") (pin "12") (pinfunction "1Y4_12") (pintype "passive"))
    )
    (net (code "100") (name "unconnected-(D2-2A1-Pad11)") (class "Default")
      (node (ref "D2") (pin "11") (pinfunction "2A1_11") (pintype "passive"))
    )
    (net (code "101") (name "unconnected-(D2-2A2-Pad13)") (class "Default")
      (node (ref "D2") (pin "13") (pinfunction "2A2_13") (pintype "passive"))
    )
    (net (code "102") (name "unconnected-(D2-2A3-Pad15)") (class "Default")
      (node (ref "D2") (pin "15") (pinfunction "2A3_15") (pintype "passive"))
    )
    (net (code "103") (name "unconnected-(D2-2A4-Pad17)") (class "Default")
      (node (ref "D2") (pin "17") (pinfunction "2A4_17") (pintype "passive"))
    )
    (net (code "104") (name "unconnected-(D2-2Y1-Pad9)") (class "Default")
      (node (ref "D2") (pin "9") (pinfunction "2Y1_9") (pintype "passive"))
    )
    (net (code "105") (name "unconnected-(D2-2Y2-Pad7)") (class "Default")
      (node (ref "D2") (pin "7") (pinfunction "2Y2_7") (pintype "passive"))
    )
    (net (code "106") (name "unconnected-(D2-2Y3-Pad5)") (class "Default")
      (node (ref "D2") (pin "5") (pinfunction "2Y3_5") (pintype "passive"))
    )
    (net (code "107") (name "unconnected-(D2-2Y4-Pad3)") (class "Default")
      (node (ref "D2") (pin "3") (pinfunction "2Y4_3") (pintype "passive"))
    )
    (net (code "108") (name "unconnected-(D2-{slash}2OE-Pad19)") (class "Default")
      (node (ref "D2") (pin "19") (pinfunction "/2OE_19") (pintype "passive"))
    )
    (net (code "109") (name "unconnected-(D6-A-Pad8)") (class "Default")
      (node (ref "D6") (pin "8") (pinfunction "A_8") (pintype "passive"))
    )
    (net (code "110") (name "unconnected-(D7-NC-Pad4)") (class "Default")
      (node (ref "D7") (pin "4") (pinfunction "NC_4") (pintype "passive"))
    )
    (net (code "111") (name "unconnected-(D7-NC-Pad5)") (class "Default")
      (node (ref "D7") (pin "5") (pinfunction "NC_5") (pintype "passive"))
    )
    (net (code "112") (name "unconnected-(D7-NC-Pad6)") (class "Default")
      (node (ref "D7") (pin "6") (pinfunction "NC_6") (pintype "passive"))
    )
    (net (code "113") (name "unconnected-(D7-NC-Pad7)") (class "Default")
      (node (ref "D7") (pin "7") (pinfunction "NC_7") (pintype "passive"))
    )
    (net (code "114") (name "unconnected-(D7-NC-Pad8)") (class "Default")
      (node (ref "D7") (pin "8") (pinfunction "NC_8") (pintype "passive"))
    )
    (net (code "115") (name "unconnected-(D7-NC-Pad9)") (class "Default")
      (node (ref "D7") (pin "9") (pinfunction "NC_9") (pintype "passive"))
    )
    (net (code "116") (name "unconnected-(D7-NC-Pad10)") (class "Default")
      (node (ref "D7") (pin "10") (pinfunction "NC_10") (pintype "passive"))
    )
    (net (code "117") (name "unconnected-(D7-NC-Pad14)") (class "Default")
      (node (ref "D7") (pin "14") (pinfunction "NC_14") (pintype "passive"))
    )
    (net (code "118") (name "unconnected-(D7-NC-Pad16)") (class "Default")
      (node (ref "D7") (pin "16") (pinfunction "NC_16") (pintype "passive"))
    )
    (net (code "119") (name "unconnected-(D7-NC-Pad17)") (class "Default")
      (node (ref "D7") (pin "17") (pinfunction "NC_17") (pintype "passive"))
    )
    (net (code "120") (name "unconnected-(D7-NC-Pad18)") (class "Default")
      (node (ref "D7") (pin "18") (pinfunction "NC_18") (pintype "passive"))
    )
    (net (code "121") (name "unconnected-(D7-NC-Pad19)") (class "Default")
      (node (ref "D7") (pin "19") (pinfunction "NC_19") (pintype "passive"))
    )
    (net (code "122") (name "unconnected-(D7-NC-Pad20)") (class "Default")
      (node (ref "D7") (pin "20") (pinfunction "NC_20") (pintype "passive"))
    )
    (net (code "123") (name "unconnected-(D7-NC-Pad21)") (class "Default")
      (node (ref "D7") (pin "21") (pinfunction "NC_21") (pintype "passive"))
    )
    (net (code "124") (name "unconnected-(D9-NC-Pad1)") (class "Default")
      (node (ref "D9") (pin "1") (pinfunction "NC_1") (pintype "passive"))
    )
    (net (code "125") (name "unconnected-(D9-NC-Pad7)") (class "Default")
      (node (ref "D9") (pin "7") (pinfunction "NC_7") (pintype "passive"))
    )
    (net (code "126") (name "unconnected-(D9-SELECT-Pad8)") (class "Default")
      (node (ref "D9") (pin "8") (pinfunction "SELECT_8") (pintype "passive"))
    )
    (net (code "127") (name "unconnected-(D9-TEMP-Pad3)") (class "Default")
      (node (ref "D9") (pin "3") (pinfunction "TEMP_3") (pintype "passive"))
    )
    (net (code "128") (name "unconnected-(D9-TRIM-Pad5)") (class "Default")
      (node (ref "D9") (pin "5") (pinfunction "TRIM_5") (pintype "passive"))
    )
    (net (code "129") (name "unconnected-(R6-Pad3)") (class "Default")
      (node (ref "R6") (pin "3") (pinfunction "3_3") (pintype "passive"))
    )
    (net (code "130") (name "unconnected-(X2-F15-Pad25)") (class "Default")
      (node (ref "X2") (pin "25") (pinfunction "F15_25") (pintype "passive"))
    )
    (net (code "131") (name "unconnected-(X2-G15-Pad21)") (class "Default")
      (node (ref "X2") (pin "21") (pinfunction "G15_21") (pintype "passive"))
    )
    (net (code "132") (name "unconnected-(X2-G16-Pad22)") (class "Default")
      (node (ref "X2") (pin "22") (pinfunction "G16_22") (pintype "passive"))
    )
    (net (code "133") (name "unconnected-(X2-J15-Pad20)") (class "Default")
      (node (ref "X2") (pin "20") (pinfunction "J15_20") (pintype "passive"))
    )
    (net (code "134") (name "unconnected-(X2-K15-Pad18)") (class "Default")
      (node (ref "X2") (pin "18") (pinfunction "K15_18") (pintype "passive"))
    )
    (net (code "135") (name "unconnected-(X2-L15-Pad16)") (class "Default")
      (node (ref "X2") (pin "16") (pinfunction "L15_16") (pintype "passive"))
    )
    (net (code "136") (name "unconnected-(X2-L16-Pad15)") (class "Default")
      (node (ref "X2") (pin "15") (pinfunction "L16_15") (pintype "passive"))
    )
    (net (code "137") (name "unconnected-(X2-N15-Pad14)") (class "Default")
      (node (ref "X2") (pin "14") (pinfunction "N15_14") (pintype "passive"))
    )
    (net (code "138") (name "unconnected-(X2-P16-Pad11)") (class "Default")
      (node (ref "X2") (pin "11") (pinfunction "P16_11") (pintype "passive"))
    )
    (net (code "139") (name "unconnected-(X2-R12-Pad3)") (class "Default")
      (node (ref "X2") (pin "3") (pinfunction "R12_3") (pintype "passive"))
    )
    (net (code "140") (name "unconnected-(X2-R13-Pad5)") (class "Default")
      (node (ref "X2") (pin "5") (pinfunction "R13_5") (pintype "passive"))
    )
    (net (code "141") (name "unconnected-(X2-R14-Pad7)") (class "Default")
      (node (ref "X2") (pin "7") (pinfunction "R14_7") (pintype "passive"))
    )
    (net (code "142") (name "unconnected-(X2-T12-Pad4)") (class "Default")
      (node (ref "X2") (pin "4") (pinfunction "T12_4") (pintype "passive"))
    )
    (net (code "143") (name "unconnected-(X2-T13-Pad6)") (class "Default")
      (node (ref "X2") (pin "6") (pinfunction "T13_6") (pintype "passive"))
    )
    (net (code "144") (name "unconnected-(X2-T14-Pad8)") (class "Default")
      (node (ref "X2") (pin "8") (pinfunction "T14_8") (pintype "passive"))
    )
    (net (code "145") (name "unconnected-(X2-VCC33-Pad2)") (class "Default")
      (node (ref "X2") (pin "2") (pinfunction "VCC33_2") (pintype "passive"))
    )
    (net (code "146") (name "unconnected-(X3-A2-Pad33)") (class "Default")
      (node (ref "X3") (pin "33") (pinfunction "A2_33") (pintype "passive"))
    )
    (net (code "147") (name "unconnected-(X3-A3-Pad35)") (class "Default")
      (node (ref "X3") (pin "35") (pinfunction "A3_35") (pintype "passive"))
    )
    (net (code "148") (name "unconnected-(X3-A4-Pad37)") (class "Default")
      (node (ref "X3") (pin "37") (pinfunction "A4_37") (pintype "passive"))
    )
    (net (code "149") (name "unconnected-(X3-A5-Pad39)") (class "Default")
      (node (ref "X3") (pin "39") (pinfunction "A5_39") (pintype "passive"))
    )
    (net (code "150") (name "unconnected-(X3-A6-Pad41)") (class "Default")
      (node (ref "X3") (pin "41") (pinfunction "A6_41") (pintype "passive"))
    )
    (net (code "151") (name "unconnected-(X3-B1-Pad34)") (class "Default")
      (node (ref "X3") (pin "34") (pinfunction "B1_34") (pintype "passive"))
    )
    (net (code "152") (name "unconnected-(X3-B3-Pad36)") (class "Default")
      (node (ref "X3") (pin "36") (pinfunction "B3_36") (pintype "passive"))
    )
    (net (code "153") (name "unconnected-(X3-B4-Pad38)") (class "Default")
      (node (ref "X3") (pin "38") (pinfunction "B4_38") (pintype "passive"))
    )
    (net (code "154") (name "unconnected-(X3-B5-Pad40)") (class "Default")
      (node (ref "X3") (pin "40") (pinfunction "B5_40") (pintype "passive"))
    )
    (net (code "155") (name "unconnected-(X3-B6-Pad42)") (class "Default")
      (node (ref "X3") (pin "42") (pinfunction "B6_42") (pintype "passive"))
    )
    (net (code "156") (name "unconnected-(X3-C2-Pad31)") (class "Default")
      (node (ref "X3") (pin "31") (pinfunction "C2_31") (pintype "passive"))
    )
    (net (code "157") (name "unconnected-(X3-C3-Pad46)") (class "Default")
      (node (ref "X3") (pin "46") (pinfunction "C3_46") (pintype "passive"))
    )
    (net (code "158") (name "unconnected-(X3-D1-Pad32)") (class "Default")
      (node (ref "X3") (pin "32") (pinfunction "D1_32") (pintype "passive"))
    )
    (net (code "159") (name "unconnected-(X3-D3-Pad43)") (class "Default")
      (node (ref "X3") (pin "43") (pinfunction "D3_43") (pintype "passive"))
    )
    (net (code "160") (name "unconnected-(X3-D4-Pad45)") (class "Default")
      (node (ref "X3") (pin "45") (pinfunction "D4_45") (pintype "passive"))
    )
    (net (code "161") (name "unconnected-(X3-E5-Pad53)") (class "Default")
      (node (ref "X3") (pin "53") (pinfunction "E5_53") (pintype "passive"))
    )
    (net (code "162") (name "unconnected-(X3-F1-Pad29)") (class "Default")
      (node (ref "X3") (pin "29") (pinfunction "F1_29") (pintype "passive"))
    )
    (net (code "163") (name "unconnected-(X3-F2-Pad30)") (class "Default")
      (node (ref "X3") (pin "30") (pinfunction "F2_30") (pintype "passive"))
    )
    (net (code "164") (name "unconnected-(X3-F3-Pad44)") (class "Default")
      (node (ref "X3") (pin "44") (pinfunction "F3_44") (pintype "passive"))
    )
    (net (code "165") (name "unconnected-(X3-F5-Pad51)") (class "Default")
      (node (ref "X3") (pin "51") (pinfunction "F5_51") (pintype "passive"))
    )
    (net (code "166") (name "unconnected-(X3-F6-Pad54)") (class "Default")
      (node (ref "X3") (pin "54") (pinfunction "F6_54") (pintype "passive"))
    )
    (net (code "167") (name "unconnected-(X3-F7-Pad52)") (class "Default")
      (node (ref "X3") (pin "52") (pinfunction "F7_52") (pintype "passive"))
    )
    (net (code "168") (name "unconnected-(X3-G1-Pad27)") (class "Default")
      (node (ref "X3") (pin "27") (pinfunction "G1_27") (pintype "passive"))
    )
    (net (code "169") (name "unconnected-(X3-G2-Pad28)") (class "Default")
      (node (ref "X3") (pin "28") (pinfunction "G2_28") (pintype "passive"))
    )
    (net (code "170") (name "unconnected-(X3-G5-Pad49)") (class "Default")
      (node (ref "X3") (pin "49") (pinfunction "G5_49") (pintype "passive"))
    )
    (net (code "171") (name "unconnected-(X3-J1-Pad25)") (class "Default")
      (node (ref "X3") (pin "25") (pinfunction "J1_25") (pintype "passive"))
    )
    (net (code "172") (name "unconnected-(X3-J2-Pad26)") (class "Default")
      (node (ref "X3") (pin "26") (pinfunction "J2_26") (pintype "passive"))
    )
    (net (code "173") (name "unconnected-(X3-J6-Pad50)") (class "Default")
      (node (ref "X3") (pin "50") (pinfunction "J6_50") (pintype "passive"))
    )
    (net (code "174") (name "unconnected-(X3-K1-Pad21)") (class "Default")
      (node (ref "X3") (pin "21") (pinfunction "K1_21") (pintype "passive"))
    )
    (net (code "175") (name "unconnected-(X3-K2-Pad22)") (class "Default")
      (node (ref "X3") (pin "22") (pinfunction "K2_22") (pintype "passive"))
    )
    (net (code "176") (name "unconnected-(X3-K5-Pad47)") (class "Default")
      (node (ref "X3") (pin "47") (pinfunction "K5_47") (pintype "passive"))
    )
    (net (code "177") (name "unconnected-(X3-K6-Pad48)") (class "Default")
      (node (ref "X3") (pin "48") (pinfunction "K6_48") (pintype "passive"))
    )
    (net (code "178") (name "unconnected-(X3-L1-Pad19)") (class "Default")
      (node (ref "X3") (pin "19") (pinfunction "L1_19") (pintype "passive"))
    )
    (net (code "179") (name "unconnected-(X3-L2-Pad20)") (class "Default")
      (node (ref "X3") (pin "20") (pinfunction "L2_20") (pintype "passive"))
    )
    (net (code "180") (name "unconnected-(X3-L3-Pad11)") (class "Default")
      (node (ref "X3") (pin "11") (pinfunction "L3_11") (pintype "passive"))
    )
    (net (code "181") (name "unconnected-(X3-L4-Pad12)") (class "Default")
      (node (ref "X3") (pin "12") (pinfunction "L4_12") (pintype "passive"))
    )
    (net (code "182") (name "unconnected-(X3-L6-Pad4)") (class "Default")
      (node (ref "X3") (pin "4") (pinfunction "L6_4") (pintype "passive"))
    )
    (net (code "183") (name "unconnected-(X3-N1-Pad17)") (class "Default")
      (node (ref "X3") (pin "17") (pinfunction "N1_17") (pintype "passive"))
    )
    (net (code "184") (name "unconnected-(X3-N2-Pad18)") (class "Default")
      (node (ref "X3") (pin "18") (pinfunction "N2_18") (pintype "passive"))
    )
    (net (code "185") (name "unconnected-(X3-N6-Pad8)") (class "Default")
      (node (ref "X3") (pin "8") (pinfunction "N6_8") (pintype "passive"))
    )
    (net (code "186") (name "unconnected-(X3-N8-Pad3)") (class "Default")
      (node (ref "X3") (pin "3") (pinfunction "N8_3") (pintype "passive"))
    )
    (net (code "187") (name "unconnected-(X3-P1-Pad15)") (class "Default")
      (node (ref "X3") (pin "15") (pinfunction "P1_15") (pintype "passive"))
    )
    (net (code "188") (name "unconnected-(X3-P2-Pad16)") (class "Default")
      (node (ref "X3") (pin "16") (pinfunction "P2_16") (pintype "passive"))
    )
    (net (code "189") (name "unconnected-(X3-P3-Pad10)") (class "Default")
      (node (ref "X3") (pin "10") (pinfunction "P3_10") (pintype "passive"))
    )
    (net (code "190") (name "unconnected-(X3-P6-Pad5)") (class "Default")
      (node (ref "X3") (pin "5") (pinfunction "P6_5") (pintype "passive"))
    )
    (net (code "191") (name "unconnected-(X3-P8-Pad6)") (class "Default")
      (node (ref "X3") (pin "6") (pinfunction "P8_6") (pintype "passive"))
    )
    (net (code "192") (name "unconnected-(X3-R1-Pad13)") (class "Default")
      (node (ref "X3") (pin "13") (pinfunction "R1_13") (pintype "passive"))
    )
    (net (code "193") (name "unconnected-(X3-T2-Pad14)") (class "Default")
      (node (ref "X3") (pin "14") (pinfunction "T2_14") (pintype "passive"))
    )
    (net (code "194") (name "unconnected-(X3-VCC33-Pad1)") (class "Default")
      (node (ref "X3") (pin "1") (pinfunction "VCC33_1") (pintype "passive"))
    )
    (net (code "195") (name "unconnected-(X4-K8-Pad27)") (class "Default")
      (node (ref "X4") (pin "27") (pinfunction "K8_27") (pintype "passive"))
    )
    (net (code "196") (name "unconnected-(X4-K9-Pad26)") (class "Default")
      (node (ref "X4") (pin "26") (pinfunction "K9_26") (pintype "passive"))
    )
    (net (code "197") (name "unconnected-(X4-L7-Pad31)") (class "Default")
      (node (ref "X4") (pin "31") (pinfunction "L7_31") (pintype "passive"))
    )
    (net (code "198") (name "unconnected-(X4-L8-Pad28)") (class "Default")
      (node (ref "X4") (pin "28") (pinfunction "L8_28") (pintype "passive"))
    )
    (net (code "199") (name "unconnected-(X4-L9-Pad25)") (class "Default")
      (node (ref "X4") (pin "25") (pinfunction "L9_25") (pintype "passive"))
    )
    (net (code "200") (name "unconnected-(X4-M6-Pad32)") (class "Default")
      (node (ref "X4") (pin "32") (pinfunction "M6_32") (pintype "passive"))
    )
    (net (code "201") (name "unconnected-(X4-M7-Pad30)") (class "Default")
      (node (ref "X4") (pin "30") (pinfunction "M7_30") (pintype "passive"))
    )
    (net (code "202") (name "unconnected-(X4-M8-Pad29)") (class "Default")
      (node (ref "X4") (pin "29") (pinfunction "M8_29") (pintype "passive"))
    )
    (net (code "203") (name "unconnected-(X4-M9-Pad24)") (class "Default")
      (node (ref "X4") (pin "24") (pinfunction "M9_24") (pintype "passive"))
    )
    (net (code "204") (name "unconnected-(X4-N9-Pad5)") (class "Default")
      (node (ref "X4") (pin "5") (pinfunction "N9_5") (pintype "passive"))
    )
    (net (code "205") (name "unconnected-(X4-N11-Pad3)") (class "Default")
      (node (ref "X4") (pin "3") (pinfunction "N11_3") (pintype "passive"))
    )
    (net (code "206") (name "unconnected-(X4-N12-Pad1)") (class "Default")
      (node (ref "X4") (pin "1") (pinfunction "N12_1") (pintype "passive"))
    )
    (net (code "207") (name "unconnected-(X4-P9-Pad6)") (class "Default")
      (node (ref "X4") (pin "6") (pinfunction "P9_6") (pintype "passive"))
    )
    (net (code "208") (name "unconnected-(X4-P11-Pad4)") (class "Default")
      (node (ref "X4") (pin "4") (pinfunction "P11_4") (pintype "passive"))
    )
    (net (code "209") (name "unconnected-(X4-R3-Pad22)") (class "Default")
      (node (ref "X4") (pin "22") (pinfunction "R3_22") (pintype "passive"))
    )
    (net (code "210") (name "unconnected-(X4-R4-Pad20)") (class "Default")
      (node (ref "X4") (pin "20") (pinfunction "R4_20") (pintype "passive"))
    )
    (net (code "211") (name "unconnected-(X4-R5-Pad18)") (class "Default")
      (node (ref "X4") (pin "18") (pinfunction "R5_18") (pintype "passive"))
    )
    (net (code "212") (name "unconnected-(X4-R6-Pad16)") (class "Default")
      (node (ref "X4") (pin "16") (pinfunction "R6_16") (pintype "passive"))
    )
    (net (code "213") (name "unconnected-(X4-R7-Pad14)") (class "Default")
      (node (ref "X4") (pin "14") (pinfunction "R7_14") (pintype "passive"))
    )
    (net (code "214") (name "unconnected-(X4-R8-Pad12)") (class "Default")
      (node (ref "X4") (pin "12") (pinfunction "R8_12") (pintype "passive"))
    )
    (net (code "215") (name "unconnected-(X4-R9-Pad10)") (class "Default")
      (node (ref "X4") (pin "10") (pinfunction "R9_10") (pintype "passive"))
    )
    (net (code "216") (name "unconnected-(X4-R10-Pad8)") (class "Default")
      (node (ref "X4") (pin "8") (pinfunction "R10_8") (pintype "passive"))
    )
    (net (code "217") (name "unconnected-(X4-R11-Pad2)") (class "Default")
      (node (ref "X4") (pin "2") (pinfunction "R11_2") (pintype "passive"))
    )
    (net (code "218") (name "unconnected-(X4-T3-Pad23)") (class "Default")
      (node (ref "X4") (pin "23") (pinfunction "T3_23") (pintype "passive"))
    )
    (net (code "219") (name "unconnected-(X4-T4-Pad21)") (class "Default")
      (node (ref "X4") (pin "21") (pinfunction "T4_21") (pintype "passive"))
    )
    (net (code "220") (name "unconnected-(X4-T5-Pad19)") (class "Default")
      (node (ref "X4") (pin "19") (pinfunction "T5_19") (pintype "passive"))
    )
    (net (code "221") (name "unconnected-(X4-T6-Pad17)") (class "Default")
      (node (ref "X4") (pin "17") (pinfunction "T6_17") (pintype "passive"))
    )
    (net (code "222") (name "unconnected-(X4-T7-Pad15)") (class "Default")
      (node (ref "X4") (pin "15") (pinfunction "T7_15") (pintype "passive"))
    )
    (net (code "223") (name "unconnected-(X4-T8-Pad13)") (class "Default")
      (node (ref "X4") (pin "13") (pinfunction "T8_13") (pintype "passive"))
    )
    (net (code "224") (name "unconnected-(X4-T9-Pad11)") (class "Default")
      (node (ref "X4") (pin "11") (pinfunction "T9_11") (pintype "passive"))
    )
    (net (code "225") (name "unconnected-(X4-T10-Pad9)") (class "Default")
      (node (ref "X4") (pin "9") (pinfunction "T10_9") (pintype "passive"))
    )
    (net (code "226") (name "unconnected-(X4-T11-Pad7)") (class "Default")
      (node (ref "X4") (pin "7") (pinfunction "T11_7") (pintype "passive"))
    )
    (net (code "227") (name "unconnected-(X5-A7-Pad31)") (class "Default")
      (node (ref "X5") (pin "31") (pinfunction "A7_31") (pintype "passive"))
    )
    (net (code "228") (name "unconnected-(X5-A8-Pad30)") (class "Default")
      (node (ref "X5") (pin "30") (pinfunction "A8_30") (pintype "passive"))
    )
    (net (code "229") (name "unconnected-(X5-A9-Pad28)") (class "Default")
      (node (ref "X5") (pin "28") (pinfunction "A9_28") (pintype "passive"))
    )
    (net (code "230") (name "unconnected-(X5-A10-Pad12)") (class "Default")
      (node (ref "X5") (pin "12") (pinfunction "A10_12") (pintype "passive"))
    )
    (net (code "231") (name "unconnected-(X5-A11-Pad8)") (class "Default")
      (node (ref "X5") (pin "8") (pinfunction "A11_8") (pintype "passive"))
    )
    (net (code "232") (name "unconnected-(X5-A11-Pad10)") (class "Default")
      (node (ref "X5") (pin "10") (pinfunction "A11_10") (pintype "passive"))
    )
    (net (code "233") (name "unconnected-(X5-A12-Pad9)") (class "Default")
      (node (ref "X5") (pin "9") (pinfunction "A12_9") (pintype "passive"))
    )
    (net (code "234") (name "unconnected-(X5-A13-Pad7)") (class "Default")
      (node (ref "X5") (pin "7") (pinfunction "A13_7") (pintype "passive"))
    )
    (net (code "235") (name "unconnected-(X5-A14-Pad5)") (class "Default")
      (node (ref "X5") (pin "5") (pinfunction "A14_5") (pintype "passive"))
    )
    (net (code "236") (name "unconnected-(X5-B8-Pad29)") (class "Default")
      (node (ref "X5") (pin "29") (pinfunction "B8_29") (pintype "passive"))
    )
    (net (code "237") (name "unconnected-(X5-B9-Pad27)") (class "Default")
      (node (ref "X5") (pin "27") (pinfunction "B9_27") (pintype "passive"))
    )
    (net (code "238") (name "unconnected-(X5-B11-Pad11)") (class "Default")
      (node (ref "X5") (pin "11") (pinfunction "B11_11") (pintype "passive"))
    )
    (net (code "239") (name "unconnected-(X5-B13-Pad6)") (class "Default")
      (node (ref "X5") (pin "6") (pinfunction "B13_6") (pintype "passive"))
    )
    (net (code "240") (name "unconnected-(X5-B14-Pad1)") (class "Default")
      (node (ref "X5") (pin "1") (pinfunction "B14_1") (pintype "passive"))
    )
    (net (code "241") (name "unconnected-(X5-C6-Pad26)") (class "Default")
      (node (ref "X5") (pin "26") (pinfunction "C6_26") (pintype "passive"))
    )
    (net (code "242") (name "unconnected-(X5-C8-Pad16)") (class "Default")
      (node (ref "X5") (pin "16") (pinfunction "C8_16") (pintype "passive"))
    )
    (net (code "243") (name "unconnected-(X5-C9-Pad14)") (class "Default")
      (node (ref "X5") (pin "14") (pinfunction "C9_14") (pintype "passive"))
    )
    (net (code "244") (name "unconnected-(X5-D5-Pad25)") (class "Default")
      (node (ref "X5") (pin "25") (pinfunction "D5_25") (pintype "passive"))
    )
    (net (code "245") (name "unconnected-(X5-D6-Pad23)") (class "Default")
      (node (ref "X5") (pin "23") (pinfunction "D6_23") (pintype "passive"))
    )
    (net (code "246") (name "unconnected-(X5-D8-Pad15)") (class "Default")
      (node (ref "X5") (pin "15") (pinfunction "D8_15") (pintype "passive"))
    )
    (net (code "247") (name "unconnected-(X5-D9-Pad13)") (class "Default")
      (node (ref "X5") (pin "13") (pinfunction "D9_13") (pintype "passive"))
    )
    (net (code "248") (name "unconnected-(X5-D11-Pad2)") (class "Default")
      (node (ref "X5") (pin "2") (pinfunction "D11_2") (pintype "passive"))
    )
    (net (code "249") (name "unconnected-(X5-E6-Pad32)") (class "Default")
      (node (ref "X5") (pin "32") (pinfunction "E6_32") (pintype "passive"))
    )
    (net (code "250") (name "unconnected-(X5-E7-Pad24)") (class "Default")
      (node (ref "X5") (pin "24") (pinfunction "E7_24") (pintype "passive"))
    )
    (net (code "251") (name "unconnected-(X5-E8-Pad21)") (class "Default")
      (node (ref "X5") (pin "21") (pinfunction "E8_21") (pintype "passive"))
    )
    (net (code "252") (name "unconnected-(X5-E9-Pad17)") (class "Default")
      (node (ref "X5") (pin "17") (pinfunction "E9_17") (pintype "passive"))
    )
    (net (code "253") (name "unconnected-(X5-E10-Pad18)") (class "Default")
      (node (ref "X5") (pin "18") (pinfunction "E10_18") (pintype "passive"))
    )
    (net (code "254") (name "unconnected-(X5-E11-Pad3)") (class "Default")
      (node (ref "X5") (pin "3") (pinfunction "E11_3") (pintype "passive"))
    )
    (net (code "255") (name "unconnected-(X5-F8-Pad22)") (class "Default")
      (node (ref "X5") (pin "22") (pinfunction "F8_22") (pintype "passive"))
    )
    (net (code "256") (name "unconnected-(X5-F9-Pad20)") (class "Default")
      (node (ref "X5") (pin "20") (pinfunction "F9_20") (pintype "passive"))
    )
    (net (code "257") (name "unconnected-(X5-F10-Pad4)") (class "Default")
      (node (ref "X5") (pin "4") (pinfunction "F10_4") (pintype "passive"))
    )
    (net (code "258") (name "unconnected-(X5-G11-Pad19)") (class "Default")
      (node (ref "X5") (pin "19") (pinfunction "G11_19") (pintype "passive"))
    )
  )
)
